# design.net
KiCad netlist of a schematic drawn in Altium Designer
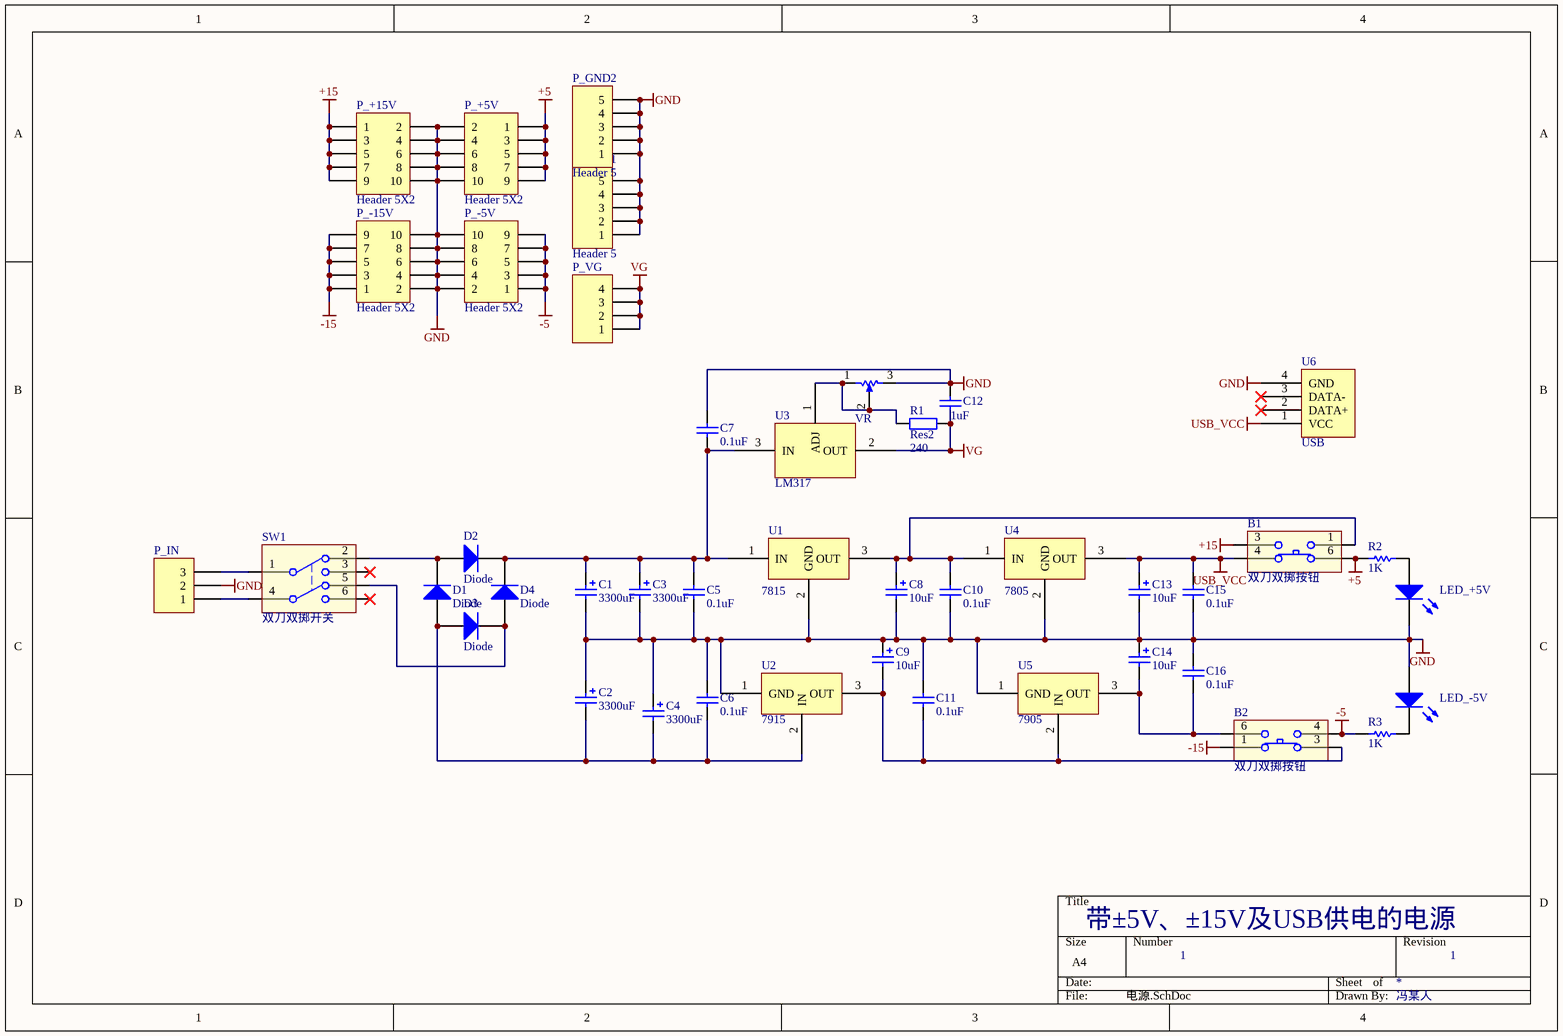
[diagram p0: 电源.SchDoc]

(export (version "E")
  (design (tool "Eeschema 10.0.6"))
  (components
    (comp (ref "B1") (value "双刀双掷按钮") (footprint "双刀双掷开关") (libsource (lib "自定义库") (part "双刀双掷按钮")))
    (comp (ref "B2") (value "双刀双掷按钮") (footprint "双刀双掷开关") (libsource (lib "") (part "双刀双掷按钮_1")))
    (comp (ref "C1")
      (value "3300uF")
      (footprint "RB7.6-15")
      (description "Polarized Capacitor (Radial)")
      (fields (field (name "Comment") "Cap Pol1") (field (name "PUBLISHER") "Altium Limited"))
      (libsource (lib "Miscellaneous Devices") (part "Cap Pol1"))
    )
    (comp (ref "C2")
      (value "3300uF")
      (footprint "RB7.6-15")
      (description "Polarized Capacitor (Radial)")
      (fields (field (name "Comment") "Cap Pol1") (field (name "PUBLISHER") "Altium Limited"))
      (libsource (lib "Miscellaneous Devices") (part "Cap Pol1"))
    )
    (comp (ref "C3")
      (value "3300uF")
      (footprint "RB7.6-15")
      (description "Polarized Capacitor (Radial)")
      (fields (field (name "Comment") "Cap Pol1") (field (name "PUBLISHER") "Altium Limited"))
      (libsource (lib "Miscellaneous Devices") (part "Cap Pol1"))
    )
    (comp (ref "C4")
      (value "3300uF")
      (footprint "RB7.6-15")
      (description "Polarized Capacitor (Radial)")
      (fields (field (name "Comment") "Cap Pol1") (field (name "PUBLISHER") "Altium Limited"))
      (libsource (lib "Miscellaneous Devices") (part "Cap Pol1"))
    )
    (comp (ref "C5")
      (value "0.1uF")
      (footprint "RAD-0.1")
      (description "Capacitor")
      (fields (field (name "Comment") "Cap") (field (name "PUBLISHER") "Altium Limited"))
      (libsource (lib "Miscellaneous Devices") (part "Cap"))
    )
    (comp (ref "C6")
      (value "0.1uF")
      (footprint "RAD-0.1")
      (description "Capacitor")
      (fields (field (name "Comment") "Cap") (field (name "PUBLISHER") "Altium Limited"))
      (libsource (lib "Miscellaneous Devices") (part "Cap"))
    )
    (comp (ref "C7")
      (value "0.1uF")
      (footprint "RAD-0.1")
      (description "Capacitor")
      (fields (field (name "Comment") "Cap") (field (name "PUBLISHER") "Altium Limited"))
      (libsource (lib "Miscellaneous Devices") (part "Cap"))
    )
    (comp (ref "C8")
      (value "10uF")
      (footprint "RAD-0.1")
      (description "Polarized Capacitor (Radial)")
      (fields (field (name "Comment") "Cap Pol1") (field (name "PUBLISHER") "Altium Limited"))
      (libsource (lib "Miscellaneous Devices") (part "Cap Pol1"))
    )
    (comp (ref "C9")
      (value "10uF")
      (footprint "RAD-0.1")
      (description "Polarized Capacitor (Radial)")
      (fields (field (name "Comment") "Cap Pol1") (field (name "PUBLISHER") "Altium Limited"))
      (libsource (lib "Miscellaneous Devices") (part "Cap Pol1"))
    )
    (comp (ref "C10")
      (value "0.1uF")
      (footprint "RAD-0.1")
      (description "Capacitor")
      (fields (field (name "Comment") "Cap") (field (name "PUBLISHER") "Altium Limited"))
      (libsource (lib "Miscellaneous Devices") (part "Cap"))
    )
    (comp (ref "C11")
      (value "0.1uF")
      (footprint "RAD-0.1")
      (description "Capacitor")
      (fields (field (name "Comment") "Cap") (field (name "PUBLISHER") "Altium Limited"))
      (libsource (lib "Miscellaneous Devices") (part "Cap"))
    )
    (comp (ref "C12")
      (value "1uF")
      (footprint "RAD-0.1")
      (description "Capacitor")
      (fields (field (name "Comment") "Cap") (field (name "PUBLISHER") "Altium Limited"))
      (libsource (lib "Miscellaneous Devices") (part "Cap"))
    )
    (comp (ref "C13")
      (value "10uF")
      (footprint "RAD-0.1")
      (description "Polarized Capacitor (Radial)")
      (fields (field (name "Comment") "Cap Pol1") (field (name "PUBLISHER") "Altium Limited"))
      (libsource (lib "Miscellaneous Devices") (part "Cap Pol1"))
    )
    (comp (ref "C14")
      (value "10uF")
      (footprint "RAD-0.1")
      (description "Polarized Capacitor (Radial)")
      (fields (field (name "Comment") "Cap Pol1") (field (name "PUBLISHER") "Altium Limited"))
      (libsource (lib "Miscellaneous Devices") (part "Cap Pol1"))
    )
    (comp (ref "C15")
      (value "0.1uF")
      (footprint "RAD-0.1")
      (description "Capacitor")
      (fields (field (name "Comment") "Cap") (field (name "PUBLISHER") "Altium Limited"))
      (libsource (lib "Miscellaneous Devices") (part "Cap"))
    )
    (comp (ref "C16")
      (value "0.1uF")
      (footprint "RAD-0.1")
      (description "Capacitor")
      (fields (field (name "Comment") "Cap") (field (name "PUBLISHER") "Altium Limited"))
      (libsource (lib "Miscellaneous Devices") (part "Cap"))
    )
    (comp (ref "D1")
      (value "Diode")
      (footprint "DO-41")
      (description "Default Diode")
      (fields (field (name "PUBLISHER") "Altium Limited"))
      (libsource (lib "自定义库") (part "Diode"))
    )
    (comp (ref "D2")
      (value "Diode")
      (footprint "DO-41")
      (description "Default Diode")
      (fields (field (name "PUBLISHER") "Altium Limited"))
      (libsource (lib "自定义库") (part "Diode"))
    )
    (comp (ref "D3")
      (value "Diode")
      (footprint "DO-41")
      (description "Default Diode")
      (fields (field (name "PUBLISHER") "Altium Limited"))
      (libsource (lib "自定义库") (part "Diode"))
    )
    (comp (ref "D4")
      (value "Diode")
      (footprint "DO-41")
      (description "Default Diode")
      (fields (field (name "PUBLISHER") "Altium Limited"))
      (libsource (lib "自定义库") (part "Diode"))
    )
    (comp (ref "LED_+5V")
      (value "LED1")
      (footprint "HDR1X2")
      (description "Typical RED GaAs LED")
      (fields (field (name "PUBLISHER") "Altium Limited"))
      (libsource (lib "Miscellaneous Devices") (part "LED1"))
    )
    (comp (ref "LED_-5V")
      (value "LED1")
      (footprint "HDR1X2")
      (description "Typical RED GaAs LED")
      (fields (field (name "PUBLISHER") "Altium Limited"))
      (libsource (lib "Miscellaneous Devices") (part "LED1"))
    )
    (comp (ref "P_+5V")
      (value "Header 5X2")
      (footprint "HDR2X5")
      (description "Header, 5-Pin, Dual row")
      (fields (field (name "PUBLISHER") "Altium Limited"))
      (libsource (lib "") (part "Header 5X2_3"))
    )
    (comp (ref "P_+15V")
      (value "Header 5X2")
      (footprint "HDR2X5")
      (description "Header, 5-Pin, Dual row")
      (fields (field (name "PUBLISHER") "Altium Limited"))
      (libsource (lib "") (part "Header 5X2_2"))
    )
    (comp (ref "P_-5V")
      (value "Header 5X2")
      (footprint "HDR2X5")
      (description "Header, 5-Pin, Dual row")
      (fields (field (name "PUBLISHER") "Altium Limited"))
      (libsource (lib "") (part "Header 5X2_1"))
    )
    (comp (ref "P_-15V")
      (value "Header 5X2")
      (footprint "HDR2X5")
      (description "Header, 5-Pin, Dual row")
      (fields (field (name "PUBLISHER") "Altium Limited"))
      (libsource (lib "Miscellaneous Connectors") (part "Header 5X2"))
    )
    (comp (ref "P_GND1")
      (value "Header 5")
      (footprint "HDR1X5")
      (description "Header, 5-Pin")
      (fields (field (name "PUBLISHER") "Altium Limited"))
      (libsource (lib "自定义库") (part "Header 5"))
    )
    (comp (ref "P_GND2")
      (value "Header 5")
      (footprint "HDR1X5")
      (description "Header, 5-Pin")
      (fields (field (name "PUBLISHER") "Altium Limited"))
      (libsource (lib "自定义库") (part "Header 5"))
    )
    (comp (ref "P_IN")
      (value "Header 3")
      (footprint "HDR1X3")
      (description "Header, 3-Pin")
      (fields (field (name "PUBLISHER") "Altium Limited"))
      (libsource (lib "Miscellaneous Connectors") (part "Header 3"))
    )
    (comp (ref "P_VG")
      (value "Header 4")
      (footprint "HDR1X4")
      (description "Header, 4-Pin")
      (fields (field (name "PUBLISHER") "Altium Limited"))
      (libsource (lib "Miscellaneous Connectors") (part "Header 4"))
    )
    (comp (ref "R1")
      (value "Res2")
      (footprint "AXIAL-0.3")
      (description "Resistor")
      (fields (field (name "ALTIUM_VALUE") "240") (field (name "PUBLISHER") "Altium Limited"))
      (libsource (lib "Miscellaneous Devices") (part "Res2"))
    )
    (comp (ref "R2")
      (value "1K")
      (footprint "AXIAL-0.3")
      (description "Semiconductor Resistor")
      (fields (field (name "Comment") "Res Semi") (field (name "PUBLISHER") "Altium Limited"))
      (libsource (lib "Miscellaneous Devices") (part "Res Semi"))
    )
    (comp (ref "R3")
      (value "1K")
      (footprint "AXIAL-0.3")
      (description "Semiconductor Resistor")
      (fields (field (name "Comment") "Res Semi") (field (name "PUBLISHER") "Altium Limited"))
      (libsource (lib "Miscellaneous Devices") (part "Res Semi"))
    )
    (comp (ref "SW1") (value "双刀双掷开关") (footprint "双刀双掷开关") (libsource (lib "自定义库") (part "双刀双掷开关")))
    (comp (ref "U1") (value "7815") (footprint "HDR1X3") (libsource (lib "自定义库") (part "7815")))
    (comp (ref "U2") (value "7915") (footprint "HDR1X3") (libsource (lib "自定义库") (part "7915")))
    (comp (ref "U3") (value "LM317") (libsource (lib "自定义库") (part "LM317")))
    (comp (ref "U4") (value "7805") (footprint "HDR1X3") (libsource (lib "自定义库") (part "7805")))
    (comp (ref "U5") (value "7905") (footprint "HDR1X3") (libsource (lib "自定义库") (part "7905")))
    (comp (ref "U6") (value "USB") (footprint "USB-A") (libsource (lib "自定义库") (part "USB")))
    (comp (ref "VR") (value "variable resister") (footprint "HDR1X3") (libsource (lib "自定义库") (part "vr")))
  )
  (nets
    (net (code "1") (name "+5") (class "Default")
      (node (ref "B1") (pin "6") (pinfunction "6_6") (pintype "passive"))
      (node (ref "P_+5V") (pin "1") (pinfunction "1_1") (pintype "passive"))
      (node (ref "P_+5V") (pin "3") (pinfunction "3_3") (pintype "passive"))
      (node (ref "P_+5V") (pin "5") (pinfunction "5_5") (pintype "passive"))
      (node (ref "P_+5V") (pin "7") (pinfunction "7_7") (pintype "passive"))
      (node (ref "P_+5V") (pin "9") (pinfunction "9_9") (pintype "passive"))
      (node (ref "R2") (pin "2") (pinfunction "2_2") (pintype "passive"))
    )
    (net (code "2") (name "+15") (class "Default")
      (node (ref "B1") (pin "3") (pinfunction "3_3") (pintype "passive"))
      (node (ref "P_+15V") (pin "1") (pinfunction "1_1") (pintype "passive"))
      (node (ref "P_+15V") (pin "3") (pinfunction "3_3") (pintype "passive"))
      (node (ref "P_+15V") (pin "5") (pinfunction "5_5") (pintype "passive"))
      (node (ref "P_+15V") (pin "7") (pinfunction "7_7") (pintype "passive"))
      (node (ref "P_+15V") (pin "9") (pinfunction "9_9") (pintype "passive"))
    )
    (net (code "3") (name "-5") (class "Default")
      (node (ref "B2") (pin "4") (pinfunction "4_4") (pintype "passive"))
      (node (ref "P_-5V") (pin "1") (pinfunction "1_1") (pintype "passive"))
      (node (ref "P_-5V") (pin "3") (pinfunction "3_3") (pintype "passive"))
      (node (ref "P_-5V") (pin "5") (pinfunction "5_5") (pintype "passive"))
      (node (ref "P_-5V") (pin "7") (pinfunction "7_7") (pintype "passive"))
      (node (ref "P_-5V") (pin "9") (pinfunction "9_9") (pintype "passive"))
      (node (ref "R3") (pin "2") (pinfunction "2_2") (pintype "passive"))
    )
    (net (code "4") (name "-15") (class "Default")
      (node (ref "B2") (pin "1") (pinfunction "1_1") (pintype "passive"))
      (node (ref "P_-15V") (pin "1") (pinfunction "1_1") (pintype "passive"))
      (node (ref "P_-15V") (pin "3") (pinfunction "3_3") (pintype "passive"))
      (node (ref "P_-15V") (pin "5") (pinfunction "5_5") (pintype "passive"))
      (node (ref "P_-15V") (pin "7") (pinfunction "7_7") (pintype "passive"))
      (node (ref "P_-15V") (pin "9") (pinfunction "9_9") (pintype "passive"))
    )
    (net (code "5") (name "GND") (class "Default")
      (node (ref "C1") (pin "2") (pinfunction "2_2") (pintype "passive"))
      (node (ref "C10") (pin "1") (pinfunction "1_1") (pintype "passive"))
      (node (ref "C11") (pin "2") (pinfunction "2_2") (pintype "passive"))
      (node (ref "C12") (pin "1") (pinfunction "1_1") (pintype "passive"))
      (node (ref "C13") (pin "2") (pinfunction "2_2") (pintype "passive"))
      (node (ref "C14") (pin "1") (pinfunction "1_1") (pintype "passive"))
      (node (ref "C15") (pin "1") (pinfunction "1_1") (pintype "passive"))
      (node (ref "C16") (pin "2") (pinfunction "2_2") (pintype "passive"))
      (node (ref "C2") (pin "1") (pinfunction "1_1") (pintype "passive"))
      (node (ref "C3") (pin "2") (pinfunction "2_2") (pintype "passive"))
      (node (ref "C4") (pin "1") (pinfunction "1_1") (pintype "passive"))
      (node (ref "C5") (pin "1") (pinfunction "1_1") (pintype "passive"))
      (node (ref "C6") (pin "2") (pinfunction "2_2") (pintype "passive"))
      (node (ref "C7") (pin "2") (pinfunction "2_2") (pintype "passive"))
      (node (ref "C8") (pin "2") (pinfunction "2_2") (pintype "passive"))
      (node (ref "C9") (pin "1") (pinfunction "1_1") (pintype "passive"))
      (node (ref "LED_+5V") (pin "2") (pinfunction "K_2") (pintype "passive"))
      (node (ref "LED_-5V") (pin "1") (pinfunction "A_1") (pintype "passive"))
      (node (ref "P_+15V") (pin "10") (pinfunction "10_10") (pintype "passive"))
      (node (ref "P_+15V") (pin "2") (pinfunction "2_2") (pintype "passive"))
      (node (ref "P_+15V") (pin "4") (pinfunction "4_4") (pintype "passive"))
      (node (ref "P_+15V") (pin "6") (pinfunction "6_6") (pintype "passive"))
      (node (ref "P_+15V") (pin "8") (pinfunction "8_8") (pintype "passive"))
      (node (ref "P_+5V") (pin "10") (pinfunction "10_10") (pintype "passive"))
      (node (ref "P_+5V") (pin "2") (pinfunction "2_2") (pintype "passive"))
      (node (ref "P_+5V") (pin "4") (pinfunction "4_4") (pintype "passive"))
      (node (ref "P_+5V") (pin "6") (pinfunction "6_6") (pintype "passive"))
      (node (ref "P_+5V") (pin "8") (pinfunction "8_8") (pintype "passive"))
      (node (ref "P_-15V") (pin "10") (pinfunction "10_10") (pintype "passive"))
      (node (ref "P_-15V") (pin "2") (pinfunction "2_2") (pintype "passive"))
      (node (ref "P_-15V") (pin "4") (pinfunction "4_4") (pintype "passive"))
      (node (ref "P_-15V") (pin "6") (pinfunction "6_6") (pintype "passive"))
      (node (ref "P_-15V") (pin "8") (pinfunction "8_8") (pintype "passive"))
      (node (ref "P_-5V") (pin "10") (pinfunction "10_10") (pintype "passive"))
      (node (ref "P_-5V") (pin "2") (pinfunction "2_2") (pintype "passive"))
      (node (ref "P_-5V") (pin "4") (pinfunction "4_4") (pintype "passive"))
      (node (ref "P_-5V") (pin "6") (pinfunction "6_6") (pintype "passive"))
      (node (ref "P_-5V") (pin "8") (pinfunction "8_8") (pintype "passive"))
      (node (ref "P_GND1") (pin "1") (pinfunction "1_1") (pintype "passive"))
      (node (ref "P_GND1") (pin "2") (pinfunction "2_2") (pintype "passive"))
      (node (ref "P_GND1") (pin "3") (pinfunction "3_3") (pintype "passive"))
      (node (ref "P_GND1") (pin "4") (pinfunction "4_4") (pintype "passive"))
      (node (ref "P_GND1") (pin "5") (pinfunction "5_5") (pintype "passive"))
      (node (ref "P_GND2") (pin "1") (pinfunction "1_1") (pintype "passive"))
      (node (ref "P_GND2") (pin "2") (pinfunction "2_2") (pintype "passive"))
      (node (ref "P_GND2") (pin "3") (pinfunction "3_3") (pintype "passive"))
      (node (ref "P_GND2") (pin "4") (pinfunction "4_4") (pintype "passive"))
      (node (ref "P_GND2") (pin "5") (pinfunction "5_5") (pintype "passive"))
      (node (ref "P_IN") (pin "2") (pinfunction "2_2") (pintype "passive"))
      (node (ref "U1") (pin "2") (pinfunction "GND_2") (pintype "passive"))
      (node (ref "U2") (pin "1") (pinfunction "GND_1") (pintype "passive"))
      (node (ref "U4") (pin "2") (pinfunction "GND_2") (pintype "passive"))
      (node (ref "U5") (pin "1") (pinfunction "GND_1") (pintype "passive"))
      (node (ref "U6") (pin "4") (pinfunction "GND_4") (pintype "passive"))
      (node (ref "VR") (pin "3") (pinfunction "ADJ_3") (pintype "passive"))
    )
    (net (code "6") (name "Net-(D1-A)") (class "Default")
      (node (ref "C2") (pin "2") (pinfunction "2_2") (pintype "passive"))
      (node (ref "C4") (pin "2") (pinfunction "2_2") (pintype "passive"))
      (node (ref "C6") (pin "1") (pinfunction "1_1") (pintype "passive"))
      (node (ref "D1") (pin "1") (pinfunction "A_1") (pintype "passive"))
      (node (ref "D3") (pin "1") (pinfunction "A_1") (pintype "passive"))
      (node (ref "U2") (pin "2") (pinfunction "IN_2") (pintype "passive"))
    )
    (net (code "7") (name "Net-(D1-K)") (class "Default")
      (node (ref "D1") (pin "2") (pinfunction "K_2") (pintype "passive"))
      (node (ref "D2") (pin "1") (pinfunction "A_1") (pintype "passive"))
      (node (ref "SW1") (pin "2") (pinfunction "2_2") (pintype "passive"))
    )
    (net (code "8") (name "Net-(D2-K)") (class "Default")
      (node (ref "C1") (pin "1") (pinfunction "1_1") (pintype "passive"))
      (node (ref "C3") (pin "1") (pinfunction "1_1") (pintype "passive"))
      (node (ref "C5") (pin "2") (pinfunction "2_2") (pintype "passive"))
      (node (ref "C7") (pin "1") (pinfunction "1_1") (pintype "passive"))
      (node (ref "D2") (pin "2") (pinfunction "K_2") (pintype "passive"))
      (node (ref "D4") (pin "2") (pinfunction "K_2") (pintype "passive"))
      (node (ref "U1") (pin "1") (pinfunction "IN_1") (pintype "passive"))
      (node (ref "U3") (pin "3") (pinfunction "IN_3") (pintype "passive"))
    )
    (net (code "9") (name "Net-(D3-K)") (class "Default")
      (node (ref "D3") (pin "2") (pinfunction "K_2") (pintype "passive"))
      (node (ref "D4") (pin "1") (pinfunction "A_1") (pintype "passive"))
      (node (ref "SW1") (pin "5") (pinfunction "5_5") (pintype "passive"))
    )
    (net (code "10") (name "Net-(LED_+5V-A)") (class "Default")
      (node (ref "LED_+5V") (pin "1") (pinfunction "A_1") (pintype "passive"))
      (node (ref "R2") (pin "1") (pinfunction "1_1") (pintype "passive"))
    )
    (net (code "11") (name "Net-(LED_-5V-K)") (class "Default")
      (node (ref "LED_-5V") (pin "2") (pinfunction "K_2") (pintype "passive"))
      (node (ref "R3") (pin "1") (pinfunction "1_1") (pintype "passive"))
    )
    (net (code "12") (name "Net-(P_IN-Pad1)") (class "Default")
      (node (ref "P_IN") (pin "1") (pinfunction "1_1") (pintype "passive"))
      (node (ref "SW1") (pin "4") (pinfunction "4_4") (pintype "passive"))
    )
    (net (code "13") (name "Net-(P_IN-Pad3)") (class "Default")
      (node (ref "P_IN") (pin "3") (pinfunction "3_3") (pintype "passive"))
      (node (ref "SW1") (pin "1") (pinfunction "1_1") (pintype "passive"))
    )
    (net (code "14") (name "Net-(U1-OUT)") (class "Default")
      (node (ref "B1") (pin "1") (pinfunction "1_1") (pintype "passive"))
      (node (ref "C10") (pin "2") (pinfunction "2_2") (pintype "passive"))
      (node (ref "C8") (pin "1") (pinfunction "1_1") (pintype "passive"))
      (node (ref "U1") (pin "3") (pinfunction "OUT_3") (pintype "passive"))
      (node (ref "U4") (pin "1") (pinfunction "IN_1") (pintype "passive"))
    )
    (net (code "15") (name "Net-(U2-OUT)") (class "Default")
      (node (ref "B2") (pin "3") (pinfunction "3_3") (pintype "passive"))
      (node (ref "C11") (pin "1") (pinfunction "1_1") (pintype "passive"))
      (node (ref "C9") (pin "2") (pinfunction "2_2") (pintype "passive"))
      (node (ref "U2") (pin "3") (pinfunction "OUT_3") (pintype "passive"))
      (node (ref "U5") (pin "2") (pinfunction "IN_2") (pintype "passive"))
    )
    (net (code "16") (name "Net-(U3-ADJ)") (class "Default")
      (node (ref "R1") (pin "2") (pinfunction "2_2") (pintype "passive"))
      (node (ref "U3") (pin "1") (pinfunction "ADJ_1") (pintype "passive"))
      (node (ref "VR") (pin "1") (pinfunction "IN_1") (pintype "passive"))
      (node (ref "VR") (pin "2") (pinfunction "OUT_2") (pintype "passive"))
    )
    (net (code "17") (name "Net-(U5-OUT)") (class "Default")
      (node (ref "B2") (pin "6") (pinfunction "6_6") (pintype "passive"))
      (node (ref "C14") (pin "2") (pinfunction "2_2") (pintype "passive"))
      (node (ref "C16") (pin "1") (pinfunction "1_1") (pintype "passive"))
      (node (ref "U5") (pin "3") (pinfunction "OUT_3") (pintype "passive"))
    )
    (net (code "18") (name "USB_VCC") (class "Default")
      (node (ref "B1") (pin "4") (pinfunction "4_4") (pintype "passive"))
      (node (ref "C13") (pin "1") (pinfunction "1_1") (pintype "passive"))
      (node (ref "C15") (pin "2") (pinfunction "2_2") (pintype "passive"))
      (node (ref "U4") (pin "3") (pinfunction "OUT_3") (pintype "passive"))
      (node (ref "U6") (pin "1") (pinfunction "VCC_1") (pintype "passive"))
    )
    (net (code "19") (name "VG") (class "Default")
      (node (ref "C12") (pin "2") (pinfunction "2_2") (pintype "passive"))
      (node (ref "P_VG") (pin "1") (pinfunction "1_1") (pintype "passive"))
      (node (ref "P_VG") (pin "2") (pinfunction "2_2") (pintype "passive"))
      (node (ref "P_VG") (pin "3") (pinfunction "3_3") (pintype "passive"))
      (node (ref "P_VG") (pin "4") (pinfunction "4_4") (pintype "passive"))
      (node (ref "R1") (pin "1") (pinfunction "1_1") (pintype "passive"))
      (node (ref "U3") (pin "2") (pinfunction "OUT_2") (pintype "passive"))
    )
    (net (code "20") (name "unconnected-(B1-Pad2)") (class "Default")
      (node (ref "B1") (pin "2") (pinfunction "2_2") (pintype "passive"))
    )
    (net (code "21") (name "unconnected-(B1-Pad5)") (class "Default")
      (node (ref "B1") (pin "5") (pinfunction "5_5") (pintype "passive"))
    )
    (net (code "22") (name "unconnected-(B2-Pad2)") (class "Default")
      (node (ref "B2") (pin "2") (pinfunction "2_2") (pintype "passive"))
    )
    (net (code "23") (name "unconnected-(B2-Pad5)") (class "Default")
      (node (ref "B2") (pin "5") (pinfunction "5_5") (pintype "passive"))
    )
    (net (code "24") (name "unconnected-(SW1-Pad3)") (class "Default")
      (node (ref "SW1") (pin "3") (pinfunction "3_3") (pintype "passive+no_connect"))
    )
    (net (code "25") (name "unconnected-(SW1-Pad6)") (class "Default")
      (node (ref "SW1") (pin "6") (pinfunction "6_6") (pintype "passive+no_connect"))
    )
    (net (code "26") (name "unconnected-(U6-DATA+-Pad2)") (class "Default")
      (node (ref "U6") (pin "2") (pinfunction "DATA+_2") (pintype "passive+no_connect"))
    )
    (net (code "27") (name "unconnected-(U6-DATA--Pad3)") (class "Default")
      (node (ref "U6") (pin "3") (pinfunction "DATA-_3") (pintype "passive+no_connect"))
    )
    (net (code "28") (name "unconnected-(U6-NC-Pad5)") (class "Default")
      (node (ref "U6") (pin "5") (pinfunction "NC_5") (pintype "passive"))
    )
    (net (code "29") (name "unconnected-(U6-NC-Pad6)") (class "Default")
      (node (ref "U6") (pin "6") (pinfunction "NC_6") (pintype "passive"))
    )
  )
)
